# User_Interface.net
KiCad netlist of a schematic drawn in Altium Designer
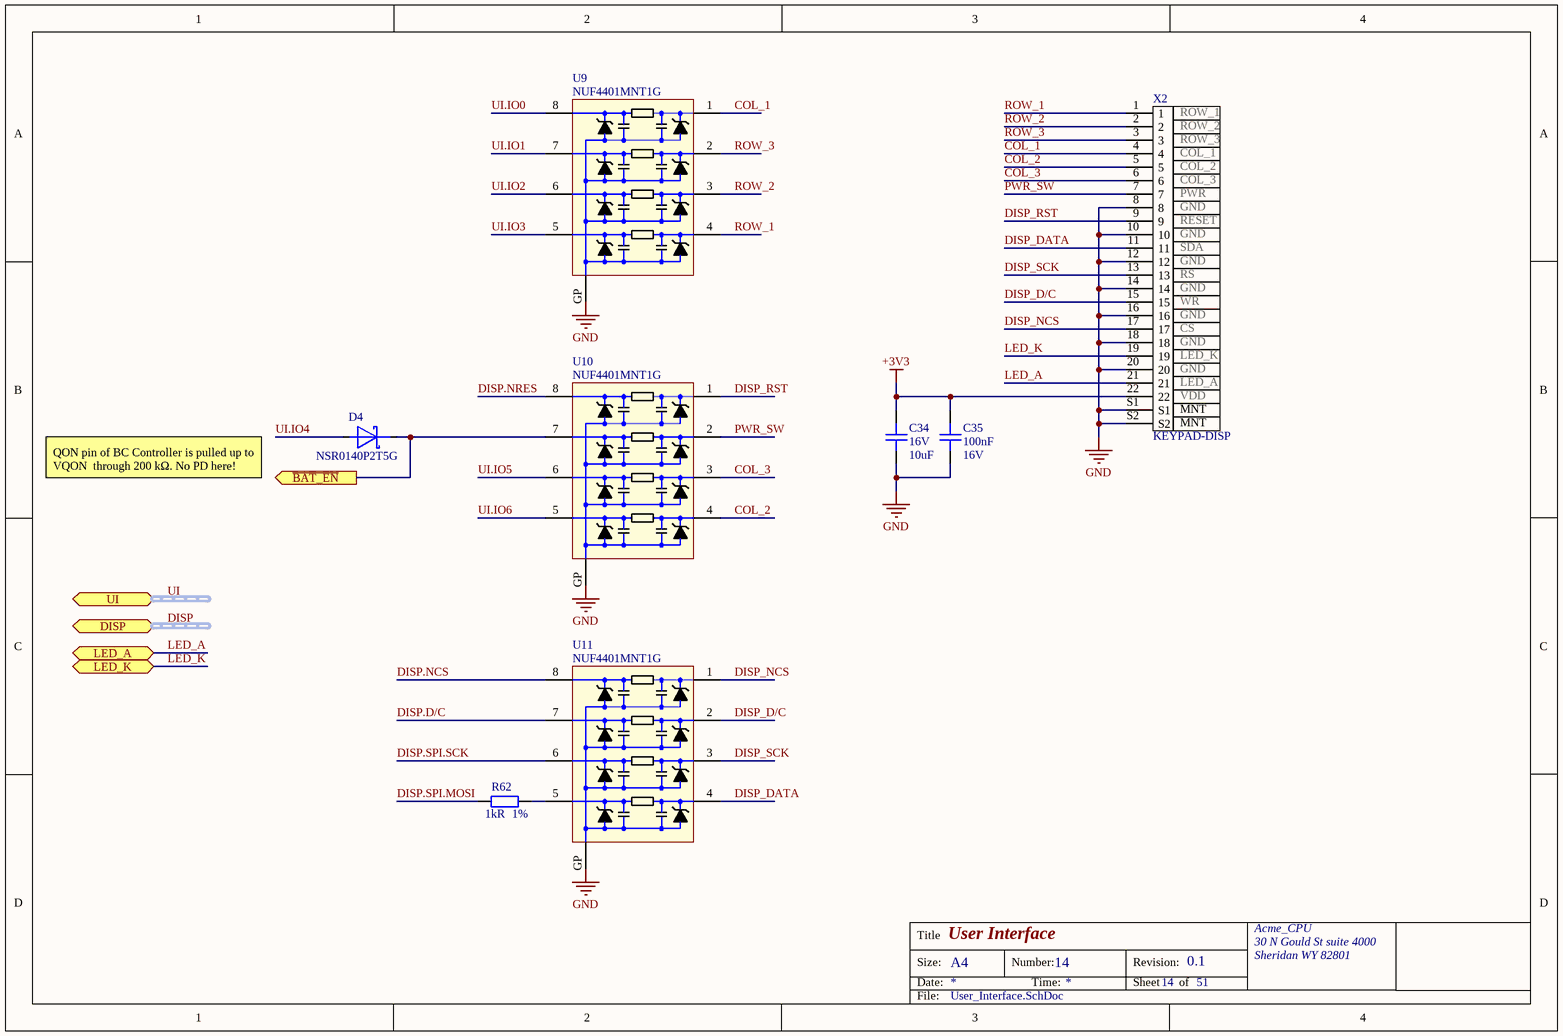
[diagram p0: User_Interface.SchDoc]

(export (version "E")
  (design (tool "Eeschema 10.0.6"))
  (components
    (comp (ref "C34")
      (value "CAP CER 10UF 16V X5R 0603")
      (footprint "C0603")
      (description "10µF ±10% 16V Ceramic Capacitor X5R 0603 (1608 Metric)")
      (fields
        (field (name "MANUFACTURER") "Murata")
        (field (name "MANUFACTURER PART NUMBER") "GRM188R61C106KAALJ")
        (field (name "VOLTAGE RATING") "16V")
        (field (name "CAPACITANCE") "10uF")
      )
      (libsource (lib "capacitors_smd") (part "CAP CER 10UF 16V X5R 0603"))
    )
    (comp (ref "C35")
      (value "CAP CER 0.1UF 16V X7R 0402")
      (footprint "C0402")
      (description "0.1µF ±10% 16V Ceramic Capacitor X7R 0402 (1005 Metric)")
      (fields
        (field (name "MANUFACTURER PART NUMBER") "CC0402KRX7R7BB104")
        (field (name "MANUFACTURER") "Yageo")
        (field (name "CAPACITANCE") "100nF")
        (field (name "VOLTAGE") "16V")
      )
      (libsource (lib "capacitors_smd") (part "CAP CER 0.1UF 16V X7R 0402"))
    )
    (comp (ref "D4")
      (value "NSR0140P2T5G")
      (footprint "SODFL100X40-2N")
      (description "Diode Schottky 30V 70mA (DC) Surface Mount SOD-923")
      (fields (field (name "MANUFACTURER") "ON Semiconductor"))
      (libsource (lib "diodes_schottky") (part "DIODE SCHOTTKY 30V 70MA SOD923"))
    )
    (comp (ref "R62")
      (value "RES SMD 1K OHM 1% 1/16W 0402")
      (footprint "R0402")
      (description "1 kOhms ±1% 0.063W, 1/16W Chip Resistor 0402 (1005 Metric) Moisture Resistant Thick Film")
      (fields
        (field (name "MANUFACTURER") "Yageo")
        (field (name "MANUFACTURER PART NUMBER") "RC0402FR-071KL")
        (field (name "TOLERANCE") "1%")
        (field (name "RESISTANCE") "1kR")
      )
      (libsource (lib "resistors_smd") (part "RES SMD 1K OHM 1% 1/16W 0402"))
    )
    (comp (ref "U9")
      (value "NUF4401MNT1G")
      (footprint "DFN8")
      (description "EMI filter w/ ESD prot. NUF4401MN 12mm r")
      (fields (field (name "MANUFACTURER") "ON Semiconductor"))
      (libsource (lib "diodes_tvs") (part "FILTER RC(PI) 200 OHM/15PF SMD"))
    )
    (comp (ref "U10")
      (value "NUF4401MNT1G")
      (footprint "DFN8")
      (description "EMI filter w/ ESD prot. NUF4401MN 12mm r")
      (fields (field (name "MANUFACTURER") "ON Semiconductor"))
      (libsource (lib "diodes_tvs") (part "FILTER RC(PI) 200 OHM/15PF SMD"))
    )
    (comp (ref "U11")
      (value "NUF4401MNT1G")
      (footprint "DFN8")
      (description "EMI filter w/ ESD prot. NUF4401MN 12mm r")
      (fields (field (name "MANUFACTURER") "ON Semiconductor"))
      (libsource (lib "diodes_tvs") (part "FILTER RC(PI) 200 OHM/15PF SMD"))
    )
    (comp (ref "X2")
      (value "KEYPAD-DISP")
      (footprint "CONN_0525592253")
      (description "22 Position FFC, FPC Connector Contacts, Vertical - 1 Sided 0.020\" (0.50mm) Surface Mount")
      (fields
        (field (name "MANUFACTURER") "Molex")
        (field (name "MANUFACTURER PART NUMBER") "52559-2253")
        (field (name "PIN_1") "ROW_1")
        (field (name "PIN_2") "ROW_2")
        (field (name "PIN_3") "ROW_3")
        (field (name "PIN_4") "COL_1")
        (field (name "PIN_5") "COL_2")
        (field (name "PIN_6") "COL_3")
        (field (name "PIN_7") "PWR")
        (field (name "PIN_8") "GND")
        (field (name "PIN_9") "RESET")
        (field (name "PIN_10") "GND")
        (field (name "PIN_11") "SDA")
        (field (name "PIN_12") "GND")
        (field (name "PIN_13") "RS")
        (field (name "PIN_14") "GND")
        (field (name "PIN_15") "WR")
        (field (name "PIN_16") "GND")
        (field (name "PIN_17") "CS")
        (field (name "PIN_18") "GND")
        (field (name "PIN_19") "LED_K")
        (field (name "PIN_20") "GND")
        (field (name "PIN_21") "LED_A")
        (field (name "PIN_22") "VDD")
        (field (name "PIN_23") "MNT")
        (field (name "PIN_24") "MNT")
      )
      (libsource (lib "connectors_ffc") (part "CONN 0525592253 FFC VERT 22POS 0.50MM SMD"))
    )
  )
  (nets
    (net (code "3") (name "+3V3") (class "Default")
      (node (ref "C34") (pin "1") (pinfunction "1_1") (pintype "passive"))
      (node (ref "C35") (pin "1") (pinfunction "1_1") (pintype "passive"))
      (node (ref "X2") (pin "22") (pinfunction "22_22") (pintype "passive"))
    )
    (net (code "4") (name "/BAT_EN") (class "Default")
      (node (ref "D4") (pin "1") (pinfunction "K_1") (pintype "passive"))
      (node (ref "U10") (pin "7") (pinfunction "OUT2_7") (pintype "passive"))
    )
    (net (code "5") (name "/COL_1") (class "Default")
      (node (ref "U9") (pin "1") (pinfunction "INP1_1") (pintype "passive"))
      (node (ref "X2") (pin "4") (pinfunction "4_4") (pintype "passive"))
    )
    (net (code "6") (name "/COL_2") (class "Default")
      (node (ref "U10") (pin "4") (pinfunction "INP4_4") (pintype "passive"))
      (node (ref "X2") (pin "5") (pinfunction "5_5") (pintype "passive"))
    )
    (net (code "7") (name "/COL_3") (class "Default")
      (node (ref "U10") (pin "3") (pinfunction "INP3_3") (pintype "passive"))
      (node (ref "X2") (pin "6") (pinfunction "6_6") (pintype "passive"))
    )
    (net (code "8") (name "/DISP.D{slash}C") (class "Default")
      (node (ref "U11") (pin "7") (pinfunction "OUT2_7") (pintype "passive"))
    )
    (net (code "9") (name "/DISP.NCS") (class "Default")
      (node (ref "U11") (pin "8") (pinfunction "OUT1_8") (pintype "passive"))
    )
    (net (code "10") (name "/DISP.NRES") (class "Default")
      (node (ref "U10") (pin "8") (pinfunction "OUT1_8") (pintype "passive"))
    )
    (net (code "11") (name "/DISP.SPI.MOSI") (class "Default")
      (node (ref "R62") (pin "1") (pinfunction "1_1") (pintype "passive"))
    )
    (net (code "12") (name "/DISP.SPI.SCK") (class "Default")
      (node (ref "U11") (pin "6") (pinfunction "OUT3_6") (pintype "passive"))
    )
    (net (code "13") (name "/DISP_DATA") (class "Default")
      (node (ref "U11") (pin "4") (pinfunction "INP4_4") (pintype "passive"))
      (node (ref "X2") (pin "11") (pinfunction "11_11") (pintype "passive"))
    )
    (net (code "14") (name "/DISP_D{slash}C") (class "Default")
      (node (ref "U11") (pin "2") (pinfunction "INP2_2") (pintype "passive"))
      (node (ref "X2") (pin "15") (pinfunction "15_15") (pintype "passive"))
    )
    (net (code "15") (name "/DISP_NCS") (class "Default")
      (node (ref "U11") (pin "1") (pinfunction "INP1_1") (pintype "passive"))
      (node (ref "X2") (pin "17") (pinfunction "17_17") (pintype "passive"))
    )
    (net (code "16") (name "/DISP_RST") (class "Default")
      (node (ref "U10") (pin "1") (pinfunction "INP1_1") (pintype "passive"))
      (node (ref "X2") (pin "9") (pinfunction "9_9") (pintype "passive"))
    )
    (net (code "17") (name "/DISP_SCK") (class "Default")
      (node (ref "U11") (pin "3") (pinfunction "INP3_3") (pintype "passive"))
      (node (ref "X2") (pin "13") (pinfunction "13_13") (pintype "passive"))
    )
    (net (code "18") (name "/LED_A") (class "Default")
      (node (ref "X2") (pin "21") (pinfunction "21_21") (pintype "passive"))
    )
    (net (code "19") (name "/LED_K") (class "Default")
      (node (ref "X2") (pin "19") (pinfunction "19_19") (pintype "passive"))
    )
    (net (code "20") (name "/PWR_SW") (class "Default")
      (node (ref "U10") (pin "2") (pinfunction "INP2_2") (pintype "passive"))
      (node (ref "X2") (pin "7") (pinfunction "7_7") (pintype "passive"))
    )
    (net (code "21") (name "/ROW_1") (class "Default")
      (node (ref "U9") (pin "4") (pinfunction "INP4_4") (pintype "passive"))
      (node (ref "X2") (pin "1") (pinfunction "1_1") (pintype "passive"))
    )
    (net (code "22") (name "/ROW_2") (class "Default")
      (node (ref "U9") (pin "3") (pinfunction "INP3_3") (pintype "passive"))
      (node (ref "X2") (pin "2") (pinfunction "2_2") (pintype "passive"))
    )
    (net (code "23") (name "/ROW_3") (class "Default")
      (node (ref "U9") (pin "2") (pinfunction "INP2_2") (pintype "passive"))
      (node (ref "X2") (pin "3") (pinfunction "3_3") (pintype "passive"))
    )
    (net (code "24") (name "/UI.IO0") (class "Default")
      (node (ref "U9") (pin "8") (pinfunction "OUT1_8") (pintype "passive"))
    )
    (net (code "25") (name "/UI.IO1") (class "Default")
      (node (ref "U9") (pin "7") (pinfunction "OUT2_7") (pintype "passive"))
    )
    (net (code "26") (name "/UI.IO2") (class "Default")
      (node (ref "U9") (pin "6") (pinfunction "OUT3_6") (pintype "passive"))
    )
    (net (code "27") (name "/UI.IO3") (class "Default")
      (node (ref "U9") (pin "5") (pinfunction "OUT4_5") (pintype "passive"))
    )
    (net (code "28") (name "/UI.IO4") (class "Default")
      (node (ref "D4") (pin "2") (pinfunction "A_2") (pintype "passive"))
    )
    (net (code "29") (name "/UI.IO5") (class "Default")
      (node (ref "U10") (pin "6") (pinfunction "OUT3_6") (pintype "passive"))
    )
    (net (code "30") (name "/UI.IO6") (class "Default")
      (node (ref "U10") (pin "5") (pinfunction "OUT4_5") (pintype "passive"))
    )
    (net (code "33") (name "GND") (class "Default")
      (node (ref "C34") (pin "2") (pinfunction "2_2") (pintype "passive"))
      (node (ref "C35") (pin "2") (pinfunction "2_2") (pintype "passive"))
      (node (ref "U10") (pin "GP") (pinfunction "GND_GP") (pintype "passive"))
      (node (ref "U11") (pin "GP") (pinfunction "GND_GP") (pintype "passive"))
      (node (ref "U9") (pin "GP") (pinfunction "GND_GP") (pintype "passive"))
      (node (ref "X2") (pin "10") (pinfunction "10_10") (pintype "passive"))
      (node (ref "X2") (pin "12") (pinfunction "12_12") (pintype "passive"))
      (node (ref "X2") (pin "14") (pinfunction "14_14") (pintype "passive"))
      (node (ref "X2") (pin "16") (pinfunction "16_16") (pintype "passive"))
      (node (ref "X2") (pin "18") (pinfunction "18_18") (pintype "passive"))
      (node (ref "X2") (pin "20") (pinfunction "20_20") (pintype "passive"))
      (node (ref "X2") (pin "8") (pinfunction "8_8") (pintype "passive"))
      (node (ref "X2") (pin "S1") (pinfunction "S1_S1") (pintype "passive"))
      (node (ref "X2") (pin "S2") (pinfunction "S2_S2") (pintype "passive"))
    )
    (net (code "34") (name "Net-(U11-OUT4)") (class "Default")
      (node (ref "R62") (pin "2") (pinfunction "2_2") (pintype "passive"))
      (node (ref "U11") (pin "5") (pinfunction "OUT4_5") (pintype "passive"))
    )
  )
)
